# lm25010.net
KiCad netlist of a schematic drawn in EAGLE
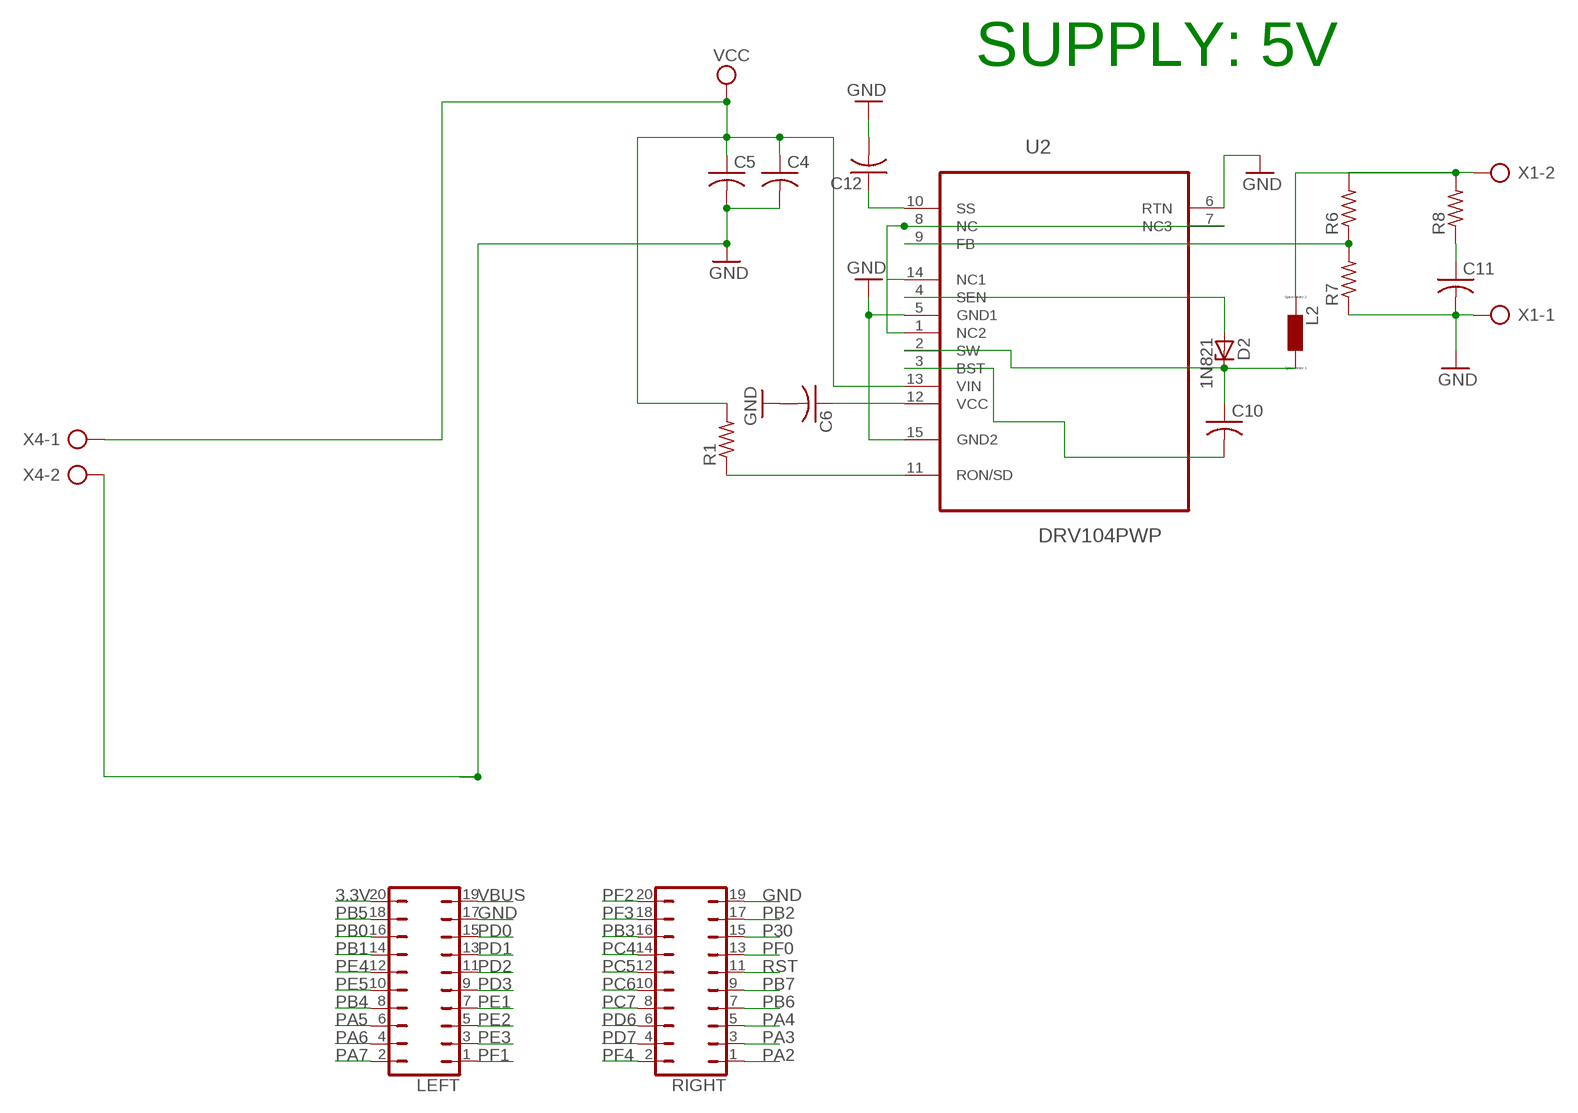
[diagram p0: schematic, sheet 1]

(export (version "E")
  (design (tool "Eeschema 10.0.6"))
  (components
    (comp (ref "C4")
      (value "C-US025-024X044")
      (footprint "eagle-import:C025-024X044")
      (libsource (lib "eagle-import") (part "C-US025-024X044"))
    )
    (comp (ref "C5")
      (value "C-US025-024X044")
      (footprint "eagle-import:C025-024X044")
      (libsource (lib "eagle-import") (part "C-US025-024X044"))
    )
    (comp (ref "C6")
      (value "C-US025-024X044")
      (footprint "eagle-import:C025-024X044")
      (libsource (lib "eagle-import") (part "C-US025-024X044"))
    )
    (comp (ref "C10")
      (value "C-US025-024X044")
      (footprint "eagle-import:C025-024X044")
      (libsource (lib "eagle-import") (part "C-US025-024X044"))
    )
    (comp (ref "C11")
      (value "C-US025-024X044")
      (footprint "eagle-import:C025-024X044")
      (libsource (lib "eagle-import") (part "C-US025-024X044"))
    )
    (comp (ref "C12")
      (value "C-US025-024X044")
      (footprint "eagle-import:C025-024X044")
      (libsource (lib "eagle-import") (part "C-US025-024X044"))
    )
    (comp (ref "D2")
      (value "1N821")
      (footprint "eagle-import:DO35Z10")
      (libsource (lib "eagle-import") (part "1N821"))
    )
    (comp (ref "L2")
      (value "L0207/10")
      (footprint "eagle-import:0207_10")
      (libsource (lib "eagle-import") (part "L0207/10"))
    )
    (comp (ref "LEFT")
      (value "JP10Q")
      (footprint "eagle-import:JP10Q")
      (libsource (lib "eagle-import") (part "JP10Q"))
    )
    (comp (ref "R1")
      (value "R-US_0207/10")
      (footprint "eagle-import:0207_10")
      (libsource (lib "eagle-import") (part "R-US_0207/10"))
    )
    (comp (ref "R6")
      (value "R-US_0207/10")
      (footprint "eagle-import:0207_10")
      (libsource (lib "eagle-import") (part "R-US_0207/10"))
    )
    (comp (ref "R7")
      (value "R-US_0207/10")
      (footprint "eagle-import:0207_10")
      (libsource (lib "eagle-import") (part "R-US_0207/10"))
    )
    (comp (ref "R8")
      (value "R-US_0207/10")
      (footprint "eagle-import:0207_10")
      (libsource (lib "eagle-import") (part "R-US_0207/10"))
    )
    (comp (ref "RIGHT")
      (value "JP10Q")
      (footprint "eagle-import:JP10Q")
      (libsource (lib "eagle-import") (part "JP10Q"))
    )
    (comp (ref "U2")
      (value "DRV104PWP")
      (footprint "eagle-import:SOP65P640X120-15N")
      (libsource (lib "eagle-import") (part "DRV104PWP"))
    )
    (comp (ref "X1")
      (value "AK300/2")
      (footprint "eagle-import:AK300_2")
      (libsource (lib "eagle-import") (part "AK300/2"))
    )
    (comp (ref "X4")
      (value "AK300/2")
      (footprint "eagle-import:AK300_2")
      (libsource (lib "eagle-import") (part "AK300/2"))
    )
  )
  (nets
    (net (code "1") (name "/3.3V") (class "Default")
      (node (ref "LEFT") (pin "20") (pinfunction "20_20") (pintype "passive"))
    )
    (net (code "2") (name "/P30") (class "Default")
      (node (ref "RIGHT") (pin "15") (pinfunction "15_15") (pintype "passive"))
    )
    (net (code "3") (name "/PA2") (class "Default")
      (node (ref "RIGHT") (pin "1") (pinfunction "1_1") (pintype "passive"))
    )
    (net (code "4") (name "/PA3") (class "Default")
      (node (ref "RIGHT") (pin "3") (pinfunction "3_3") (pintype "passive"))
    )
    (net (code "5") (name "/PA4") (class "Default")
      (node (ref "RIGHT") (pin "5") (pinfunction "5_5") (pintype "passive"))
    )
    (net (code "6") (name "/PA5") (class "Default")
      (node (ref "LEFT") (pin "6") (pinfunction "6_6") (pintype "passive"))
    )
    (net (code "7") (name "/PA6") (class "Default")
      (node (ref "LEFT") (pin "4") (pinfunction "4_4") (pintype "passive"))
    )
    (net (code "8") (name "/PA7") (class "Default")
      (node (ref "LEFT") (pin "2") (pinfunction "2_2") (pintype "passive"))
    )
    (net (code "9") (name "/PB0") (class "Default")
      (node (ref "LEFT") (pin "16") (pinfunction "16_16") (pintype "passive"))
    )
    (net (code "10") (name "/PB1") (class "Default")
      (node (ref "LEFT") (pin "14") (pinfunction "14_14") (pintype "passive"))
    )
    (net (code "11") (name "/PB2") (class "Default")
      (node (ref "RIGHT") (pin "17") (pinfunction "17_17") (pintype "passive"))
    )
    (net (code "12") (name "/PB3") (class "Default")
      (node (ref "RIGHT") (pin "16") (pinfunction "16_16") (pintype "passive"))
    )
    (net (code "13") (name "/PB4") (class "Default")
      (node (ref "LEFT") (pin "8") (pinfunction "8_8") (pintype "passive"))
    )
    (net (code "14") (name "/PB5") (class "Default")
      (node (ref "LEFT") (pin "18") (pinfunction "18_18") (pintype "passive"))
    )
    (net (code "15") (name "/PB6") (class "Default")
      (node (ref "RIGHT") (pin "7") (pinfunction "7_7") (pintype "passive"))
    )
    (net (code "16") (name "/PB7") (class "Default")
      (node (ref "RIGHT") (pin "9") (pinfunction "9_9") (pintype "passive"))
    )
    (net (code "17") (name "/PC4") (class "Default")
      (node (ref "RIGHT") (pin "14") (pinfunction "14_14") (pintype "passive"))
    )
    (net (code "18") (name "/PC5") (class "Default")
      (node (ref "RIGHT") (pin "12") (pinfunction "12_12") (pintype "passive"))
    )
    (net (code "19") (name "/PC6") (class "Default")
      (node (ref "RIGHT") (pin "10") (pinfunction "10_10") (pintype "passive"))
    )
    (net (code "20") (name "/PC7") (class "Default")
      (node (ref "RIGHT") (pin "8") (pinfunction "8_8") (pintype "passive"))
    )
    (net (code "21") (name "/PD0") (class "Default")
      (node (ref "LEFT") (pin "15") (pinfunction "15_15") (pintype "passive"))
    )
    (net (code "22") (name "/PD1") (class "Default")
      (node (ref "LEFT") (pin "13") (pinfunction "13_13") (pintype "passive"))
    )
    (net (code "23") (name "/PD2") (class "Default")
      (node (ref "LEFT") (pin "11") (pinfunction "11_11") (pintype "passive"))
    )
    (net (code "24") (name "/PD3") (class "Default")
      (node (ref "LEFT") (pin "9") (pinfunction "9_9") (pintype "passive"))
    )
    (net (code "25") (name "/PD6") (class "Default")
      (node (ref "RIGHT") (pin "6") (pinfunction "6_6") (pintype "passive"))
    )
    (net (code "26") (name "/PD7") (class "Default")
      (node (ref "RIGHT") (pin "4") (pinfunction "4_4") (pintype "passive"))
    )
    (net (code "27") (name "/PE1") (class "Default")
      (node (ref "LEFT") (pin "7") (pinfunction "7_7") (pintype "passive"))
    )
    (net (code "28") (name "/PE2") (class "Default")
      (node (ref "LEFT") (pin "5") (pinfunction "5_5") (pintype "passive"))
    )
    (net (code "29") (name "/PE3") (class "Default")
      (node (ref "LEFT") (pin "3") (pinfunction "3_3") (pintype "passive"))
    )
    (net (code "30") (name "/PE4") (class "Default")
      (node (ref "LEFT") (pin "12") (pinfunction "12_12") (pintype "passive"))
    )
    (net (code "31") (name "/PE5") (class "Default")
      (node (ref "LEFT") (pin "10") (pinfunction "10_10") (pintype "passive"))
    )
    (net (code "32") (name "/PF0") (class "Default")
      (node (ref "RIGHT") (pin "13") (pinfunction "13_13") (pintype "passive"))
    )
    (net (code "33") (name "/PF1") (class "Default")
      (node (ref "LEFT") (pin "1") (pinfunction "1_1") (pintype "passive"))
    )
    (net (code "34") (name "/PF2") (class "Default")
      (node (ref "RIGHT") (pin "20") (pinfunction "20_20") (pintype "passive"))
    )
    (net (code "35") (name "/PF3") (class "Default")
      (node (ref "RIGHT") (pin "18") (pinfunction "18_18") (pintype "passive"))
    )
    (net (code "36") (name "/PF4") (class "Default")
      (node (ref "RIGHT") (pin "2") (pinfunction "2_2") (pintype "passive"))
    )
    (net (code "37") (name "/RST") (class "Default")
      (node (ref "RIGHT") (pin "11") (pinfunction "11_11") (pintype "passive"))
    )
    (net (code "38") (name "/VBUS") (class "Default")
      (node (ref "LEFT") (pin "19") (pinfunction "19_19") (pintype "passive"))
    )
    (net (code "39") (name "GND") (class "Default")
      (node (ref "C11") (pin "2") (pinfunction "2_2") (pintype "passive"))
      (node (ref "C12") (pin "2") (pinfunction "2_2") (pintype "passive"))
      (node (ref "C4") (pin "2") (pinfunction "2_2") (pintype "passive"))
      (node (ref "C5") (pin "2") (pinfunction "2_2") (pintype "passive"))
      (node (ref "C6") (pin "2") (pinfunction "2_2") (pintype "passive"))
      (node (ref "LEFT") (pin "17") (pinfunction "17_17") (pintype "passive"))
      (node (ref "R7") (pin "1") (pinfunction "1_1") (pintype "passive"))
      (node (ref "RIGHT") (pin "19") (pinfunction "19_19") (pintype "passive"))
      (node (ref "U2") (pin "15") (pinfunction "GND2_15") (pintype "passive"))
      (node (ref "U2") (pin "5") (pinfunction "GND1_5") (pintype "passive"))
      (node (ref "U2") (pin "6") (pinfunction "RTN_6") (pintype "output"))
      (node (ref "X1") (pin "1") (pinfunction "KL_1") (pintype "passive"))
      (node (ref "X4") (pin "2") (pinfunction "KL_2") (pintype "passive"))
    )
    (net (code "40") (name "Net-(C11-Pad1)") (class "Default")
      (node (ref "C11") (pin "1") (pinfunction "1_1") (pintype "passive"))
      (node (ref "R8") (pin "1") (pinfunction "1_1") (pintype "passive"))
    )
    (net (code "41") (name "Net-(U2-BST)") (class "Default")
      (node (ref "C10") (pin "2") (pinfunction "2_2") (pintype "passive"))
      (node (ref "U2") (pin "3") (pinfunction "BST_3") (pintype "passive"))
    )
    (net (code "42") (name "Net-(U2-FB)") (class "Default")
      (node (ref "R6") (pin "1") (pinfunction "1_1") (pintype "passive"))
      (node (ref "R7") (pin "2") (pinfunction "2_2") (pintype "passive"))
      (node (ref "U2") (pin "9") (pinfunction "FB_9") (pintype "power_in"))
    )
    (net (code "43") (name "Net-(U2-NC)") (class "Default")
      (node (ref "U2") (pin "1") (pinfunction "NC2_1") (pintype "input"))
      (node (ref "U2") (pin "14") (pinfunction "NC1_14") (pintype "input"))
      (node (ref "U2") (pin "7") (pinfunction "NC3_7") (pintype "output"))
      (node (ref "U2") (pin "8") (pinfunction "NC_8") (pintype "power_in"))
    )
    (net (code "44") (name "Net-(U2-RON{slash}SD)") (class "Default")
      (node (ref "R1") (pin "1") (pinfunction "1_1") (pintype "passive"))
      (node (ref "U2") (pin "11") (pinfunction "RON/SD_11") (pintype "passive"))
    )
    (net (code "45") (name "Net-(U2-SEN)") (class "Default")
      (node (ref "D2") (pin "A") (pinfunction "A_A") (pintype "passive"))
      (node (ref "U2") (pin "4") (pinfunction "SEN_4") (pintype "passive"))
    )
    (net (code "46") (name "Net-(U2-SS)") (class "Default")
      (node (ref "C12") (pin "1") (pinfunction "1_1") (pintype "passive"))
      (node (ref "U2") (pin "10") (pinfunction "SS_10") (pintype "power_in"))
    )
    (net (code "47") (name "Net-(U2-SW)") (class "Default")
      (node (ref "C10") (pin "1") (pinfunction "1_1") (pintype "passive"))
      (node (ref "D2") (pin "C") (pinfunction "C_C") (pintype "passive"))
      (node (ref "L2") (pin "1") (pinfunction "1_1") (pintype "passive"))
      (node (ref "U2") (pin "2") (pinfunction "SW_2") (pintype "input"))
    )
    (net (code "48") (name "Net-(U2-VCC)") (class "Default")
      (node (ref "C6") (pin "1") (pinfunction "1_1") (pintype "passive"))
      (node (ref "U2") (pin "12") (pinfunction "VCC_12") (pintype "input"))
    )
    (net (code "49") (name "Net-(X1B-KL)") (class "Default")
      (node (ref "L2") (pin "2") (pinfunction "2_2") (pintype "passive"))
      (node (ref "R6") (pin "2") (pinfunction "2_2") (pintype "passive"))
      (node (ref "R8") (pin "2") (pinfunction "2_2") (pintype "passive"))
      (node (ref "X1") (pin "2") (pinfunction "KL_2") (pintype "passive"))
    )
    (net (code "50") (name "VCC") (class "Default")
      (node (ref "C4") (pin "1") (pinfunction "1_1") (pintype "passive"))
      (node (ref "C5") (pin "1") (pinfunction "1_1") (pintype "passive"))
      (node (ref "R1") (pin "2") (pinfunction "2_2") (pintype "passive"))
      (node (ref "U2") (pin "13") (pinfunction "VIN_13") (pintype "passive"))
      (node (ref "X4") (pin "1") (pinfunction "KL_1") (pintype "passive"))
    )
  )
)
